# Effects_PSU.net
KiCad netlist of a schematic drawn in Altium Designer
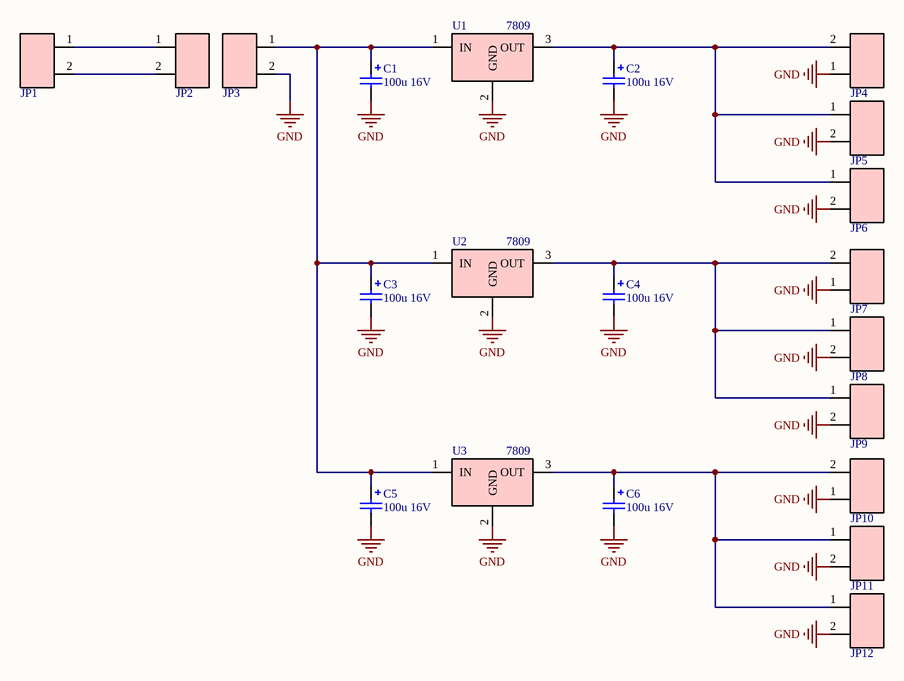
[diagram p0: Effects_PSU.SchDoc]

(export (version "E")
  (design (tool "Eeschema 10.0.6"))
  (components
    (comp (ref "C1")
      (value "100u 16V")
      (footprint "Effects_PSU:Capacitor 6.3mm")
      (libsource (lib "Effects_PSU") (part "Capacitor 100u 16V 6.3mm"))
    )
    (comp (ref "C2")
      (value "100u 16V")
      (footprint "Effects_PSU:Capacitor 6.3mm")
      (libsource (lib "Effects_PSU") (part "Capacitor 100u 16V 6.3mm"))
    )
    (comp (ref "C3")
      (value "100u 16V")
      (footprint "Effects_PSU:Capacitor 6.3mm")
      (libsource (lib "Effects_PSU") (part "Capacitor 100u 16V 6.3mm"))
    )
    (comp (ref "C4")
      (value "100u 16V")
      (footprint "Effects_PSU:Capacitor 6.3mm")
      (libsource (lib "Effects_PSU") (part "Capacitor 100u 16V 6.3mm"))
    )
    (comp (ref "C5")
      (value "100u 16V")
      (footprint "Effects_PSU:Capacitor 6.3mm")
      (libsource (lib "Effects_PSU") (part "Capacitor 100u 16V 6.3mm"))
    )
    (comp (ref "C6")
      (value "100u 16V")
      (footprint "Effects_PSU:Capacitor 6.3mm")
      (libsource (lib "Effects_PSU") (part "Capacitor 100u 16V 6.3mm"))
    )
    (comp (ref "JP1")
      (value "Mechanical 2pin 1mm")
      (footprint "Effects_PSU:2 PIN")
      (libsource (lib "") (part "Mechanical 2pin 1mm_2"))
    )
    (comp (ref "JP2")
      (value "Mechanical 2pin 1mm")
      (footprint "Effects_PSU:2 PIN")
      (libsource (lib "") (part "Mechanical 2pin 1mm_1"))
    )
    (comp (ref "JP3")
      (value "Mechanical 2pin 1mm")
      (footprint "Effects_PSU:2 PIN")
      (libsource (lib "") (part "Mechanical 2pin 1mm_2"))
    )
    (comp (ref "JP4")
      (value "Mechanical 2pin 1mm")
      (footprint "Effects_PSU:2 PIN")
      (libsource (lib "Effects_PSU") (part "Mechanical 2pin 1mm"))
    )
    (comp (ref "JP5")
      (value "Mechanical 2pin 1mm")
      (footprint "Effects_PSU:2 PIN")
      (libsource (lib "") (part "Mechanical 2pin 1mm_1"))
    )
    (comp (ref "JP6")
      (value "Mechanical 2pin 1mm")
      (footprint "Effects_PSU:2 PIN")
      (libsource (lib "") (part "Mechanical 2pin 1mm_1"))
    )
    (comp (ref "JP7")
      (value "Mechanical 2pin 1mm")
      (footprint "Effects_PSU:2 PIN")
      (libsource (lib "Effects_PSU") (part "Mechanical 2pin 1mm"))
    )
    (comp (ref "JP8")
      (value "Mechanical 2pin 1mm")
      (footprint "Effects_PSU:2 PIN")
      (libsource (lib "") (part "Mechanical 2pin 1mm_1"))
    )
    (comp (ref "JP9")
      (value "Mechanical 2pin 1mm")
      (footprint "Effects_PSU:2 PIN")
      (libsource (lib "") (part "Mechanical 2pin 1mm_1"))
    )
    (comp (ref "JP10")
      (value "Mechanical 2pin 1mm")
      (footprint "Effects_PSU:2 PIN")
      (libsource (lib "Effects_PSU") (part "Mechanical 2pin 1mm"))
    )
    (comp (ref "JP11")
      (value "Mechanical 2pin 1mm")
      (footprint "Effects_PSU:2 PIN")
      (libsource (lib "") (part "Mechanical 2pin 1mm_1"))
    )
    (comp (ref "JP12")
      (value "Mechanical 2pin 1mm")
      (footprint "Effects_PSU:2 PIN")
      (libsource (lib "") (part "Mechanical 2pin 1mm_1"))
    )
    (comp (ref "U1")
      (value "7809")
      (footprint "Effects_PSU:78xx")
      (libsource (lib "Effects_PSU") (part "IC 7809 TO-220"))
    )
    (comp (ref "U2")
      (value "7809")
      (footprint "Effects_PSU:78xx")
      (libsource (lib "Effects_PSU") (part "IC 7809 TO-220"))
    )
    (comp (ref "U3")
      (value "7809")
      (footprint "Effects_PSU:78xx")
      (libsource (lib "Effects_PSU") (part "IC 7809 TO-220"))
    )
  )
  (nets
    (net (code "1") (name "GND") (class "Default")
      (node (ref "C1") (pin "2") (pinfunction "2_2") (pintype "passive"))
      (node (ref "C2") (pin "2") (pinfunction "2_2") (pintype "passive"))
      (node (ref "C3") (pin "2") (pinfunction "2_2") (pintype "passive"))
      (node (ref "C4") (pin "2") (pinfunction "2_2") (pintype "passive"))
      (node (ref "C5") (pin "2") (pinfunction "2_2") (pintype "passive"))
      (node (ref "C6") (pin "2") (pinfunction "2_2") (pintype "passive"))
      (node (ref "JP10") (pin "1") (pinfunction "1_1") (pintype "passive"))
      (node (ref "JP11") (pin "2") (pinfunction "2_2") (pintype "passive"))
      (node (ref "JP12") (pin "2") (pinfunction "2_2") (pintype "passive"))
      (node (ref "JP3") (pin "2") (pinfunction "2_2") (pintype "passive"))
      (node (ref "JP4") (pin "1") (pinfunction "1_1") (pintype "passive"))
      (node (ref "JP5") (pin "2") (pinfunction "2_2") (pintype "passive"))
      (node (ref "JP6") (pin "2") (pinfunction "2_2") (pintype "passive"))
      (node (ref "JP7") (pin "1") (pinfunction "1_1") (pintype "passive"))
      (node (ref "JP8") (pin "2") (pinfunction "2_2") (pintype "passive"))
      (node (ref "JP9") (pin "2") (pinfunction "2_2") (pintype "passive"))
      (node (ref "U1") (pin "2") (pinfunction "GND_2") (pintype "passive"))
      (node (ref "U2") (pin "2") (pinfunction "GND_2") (pintype "passive"))
      (node (ref "U3") (pin "2") (pinfunction "GND_2") (pintype "passive"))
    )
    (net (code "2") (name "Net-(JP1-Pad1)") (class "Default")
      (node (ref "JP1") (pin "1") (pinfunction "1_1") (pintype "passive"))
      (node (ref "JP2") (pin "1") (pinfunction "1_1") (pintype "passive"))
    )
    (net (code "3") (name "Net-(JP1-Pad2)") (class "Default")
      (node (ref "JP1") (pin "2") (pinfunction "2_2") (pintype "passive"))
      (node (ref "JP2") (pin "2") (pinfunction "2_2") (pintype "passive"))
    )
    (net (code "4") (name "Net-(U1-IN)") (class "Default")
      (node (ref "C1") (pin "1") (pinfunction "1_1") (pintype "passive"))
      (node (ref "C3") (pin "1") (pinfunction "1_1") (pintype "passive"))
      (node (ref "C5") (pin "1") (pinfunction "1_1") (pintype "passive"))
      (node (ref "JP3") (pin "1") (pinfunction "1_1") (pintype "passive"))
      (node (ref "U1") (pin "1") (pinfunction "IN_1") (pintype "passive"))
      (node (ref "U2") (pin "1") (pinfunction "IN_1") (pintype "passive"))
      (node (ref "U3") (pin "1") (pinfunction "IN_1") (pintype "passive"))
    )
    (net (code "5") (name "Net-(U1-OUT)") (class "Default")
      (node (ref "C2") (pin "1") (pinfunction "1_1") (pintype "passive"))
      (node (ref "JP4") (pin "2") (pinfunction "2_2") (pintype "passive"))
      (node (ref "JP5") (pin "1") (pinfunction "1_1") (pintype "passive"))
      (node (ref "JP6") (pin "1") (pinfunction "1_1") (pintype "passive"))
      (node (ref "U1") (pin "3") (pinfunction "OUT_3") (pintype "passive"))
    )
    (net (code "6") (name "Net-(U2-OUT)") (class "Default")
      (node (ref "C4") (pin "1") (pinfunction "1_1") (pintype "passive"))
      (node (ref "JP7") (pin "2") (pinfunction "2_2") (pintype "passive"))
      (node (ref "JP8") (pin "1") (pinfunction "1_1") (pintype "passive"))
      (node (ref "JP9") (pin "1") (pinfunction "1_1") (pintype "passive"))
      (node (ref "U2") (pin "3") (pinfunction "OUT_3") (pintype "passive"))
    )
    (net (code "7") (name "Net-(U3-OUT)") (class "Default")
      (node (ref "C6") (pin "1") (pinfunction "1_1") (pintype "passive"))
      (node (ref "JP10") (pin "2") (pinfunction "2_2") (pintype "passive"))
      (node (ref "JP11") (pin "1") (pinfunction "1_1") (pintype "passive"))
      (node (ref "JP12") (pin "1") (pinfunction "1_1") (pintype "passive"))
      (node (ref "U3") (pin "3") (pinfunction "OUT_3") (pintype "passive"))
    )
  )
)
